# power_rev1.net
KiCad netlist of a schematic drawn in EAGLE
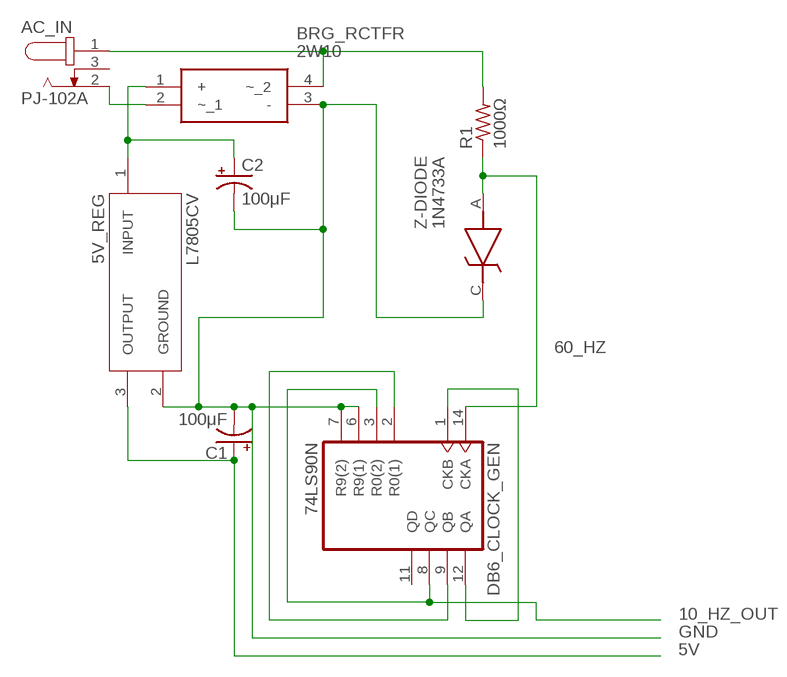
[diagram p0: schematic, sheet 1]

(export (version "E")
  (design (tool "Eeschema 10.0.6"))
  (components
    (comp (ref "5V_REG")
      (value "L7805CV")
      (footprint "eagle-import:TO255P1040X460X1968-3")
      (fields (field (name "MF") "STMicroelectronics"))
      (libsource (lib "eagle-import") (part "L7805CV"))
    )
    (comp (ref "AC_IN")
      (value "PJ-102A")
      (footprint "eagle-import:CUI_PJ-102A")
      (fields (field (name "MANUFACTURER") "CUI INC"))
      (libsource (lib "eagle-import") (part "PJ-102A"))
    )
    (comp (ref "BRG_RCTFR")
      (value "2W10")
      (footprint "eagle-import:2W10")
      (libsource (lib "eagle-import") (part "2W10"))
    )
    (comp (ref "C1")
      (value "100μF")
      (footprint "eagle-import:E2,5-6")
      (libsource (lib "eagle-import") (part "CPOL-USE2.5-6"))
    )
    (comp (ref "C2")
      (value "100μF")
      (footprint "eagle-import:E2,5-6")
      (libsource (lib "eagle-import") (part "CPOL-USE2.5-6"))
    )
    (comp (ref "DB6_CLOCK_GEN")
      (value "74LS90N")
      (footprint "eagle-import:DIL14")
      (libsource (lib "eagle-import") (part "7490NLS"))
    )
    (comp (ref "R1")
      (value "1000Ω")
      (footprint "eagle-import:0207_7")
      (libsource (lib "eagle-import") (part "R-US_0207/7"))
    )
    (comp (ref "Z-DIODE")
      (value "1N4733A")
      (footprint "eagle-import:DIOAD1125W80L520D270")
      (libsource (lib "eagle-import") (part "1N4733A"))
    )
  )
  (nets
    (net (code "1") (name "/5V") (class "Default")
      (node (ref "5V_REG") (pin "3") (pinfunction "OUTPUT_3") (pintype "output"))
      (node (ref "C1") (pin "+") (pinfunction "+_+") (pintype "passive"))
    )
    (net (code "2") (name "/10_HZ_OUT") (class "Default")
      (node (ref "DB6_CLOCK_GEN") (pin "3") (pinfunction "R0(2)_3") (pintype "input"))
      (node (ref "DB6_CLOCK_GEN") (pin "8") (pinfunction "QC_8") (pintype "output"))
    )
    (net (code "3") (name "/60_HZ") (class "Default")
      (node (ref "DB6_CLOCK_GEN") (pin "14") (pinfunction "CKA_14") (pintype "input"))
      (node (ref "R1") (pin "1") (pinfunction "1_1") (pintype "passive"))
      (node (ref "Z-DIODE") (pin "A") (pinfunction "A_A") (pintype "bidirectional"))
    )
    (net (code "4") (name "/GND") (class "Default")
      (node (ref "5V_REG") (pin "2") (pinfunction "GROUND_2") (pintype "power_in"))
      (node (ref "BRG_RCTFR") (pin "3") (pinfunction "-_3") (pintype "bidirectional"))
      (node (ref "C1") (pin "-") (pinfunction "-_-") (pintype "passive"))
      (node (ref "C2") (pin "-") (pinfunction "-_-") (pintype "passive"))
      (node (ref "DB6_CLOCK_GEN") (pin "6") (pinfunction "R9(1)_6") (pintype "input"))
      (node (ref "DB6_CLOCK_GEN") (pin "7") (pinfunction "R9(2)_7") (pintype "input"))
      (node (ref "Z-DIODE") (pin "C") (pinfunction "K_C") (pintype "bidirectional"))
    )
    (net (code "5") (name "Net-(5V_REG-INPUT)") (class "Default")
      (node (ref "5V_REG") (pin "1") (pinfunction "INPUT_1") (pintype "input"))
      (node (ref "BRG_RCTFR") (pin "1") (pinfunction "+_1") (pintype "bidirectional"))
      (node (ref "C2") (pin "+") (pinfunction "+_+") (pintype "passive"))
    )
    (net (code "6") (name "Net-(BRG_RCTFR-~{_1})") (class "Default")
      (node (ref "AC_IN") (pin "2") (pinfunction "2_2") (pintype "passive"))
      (node (ref "BRG_RCTFR") (pin "2") (pinfunction "~{_1}_2") (pintype "bidirectional"))
    )
    (net (code "7") (name "Net-(BRG_RCTFR-~{_2})") (class "Default")
      (node (ref "AC_IN") (pin "1") (pinfunction "1_1") (pintype "passive"))
      (node (ref "BRG_RCTFR") (pin "4") (pinfunction "~{_2}_4") (pintype "bidirectional"))
      (node (ref "R1") (pin "2") (pinfunction "2_2") (pintype "passive"))
    )
    (net (code "8") (name "Net-(DB6_CLOCK_GENA-CKB)") (class "Default")
      (node (ref "DB6_CLOCK_GEN") (pin "1") (pinfunction "CKB_1") (pintype "input"))
      (node (ref "DB6_CLOCK_GEN") (pin "12") (pinfunction "QA_12") (pintype "output"))
    )
    (net (code "9") (name "Net-(DB6_CLOCK_GENA-QB)") (class "Default")
      (node (ref "DB6_CLOCK_GEN") (pin "2") (pinfunction "R0(1)_2") (pintype "input"))
      (node (ref "DB6_CLOCK_GEN") (pin "9") (pinfunction "QB_9") (pintype "output"))
    )
    (net (code "10") (name "unconnected-(AC_IN-Pad3)") (class "Default")
      (node (ref "AC_IN") (pin "3") (pinfunction "3_3") (pintype "passive"))
    )
    (net (code "11") (name "unconnected-(DB6_CLOCK_GENA-QD-Pad11)") (class "Default")
      (node (ref "DB6_CLOCK_GEN") (pin "11") (pinfunction "QD_11") (pintype "output"))
    )
  )
)
